# pc_to_pc_communication.net
KiCad netlist of a schematic drawn in EAGLE
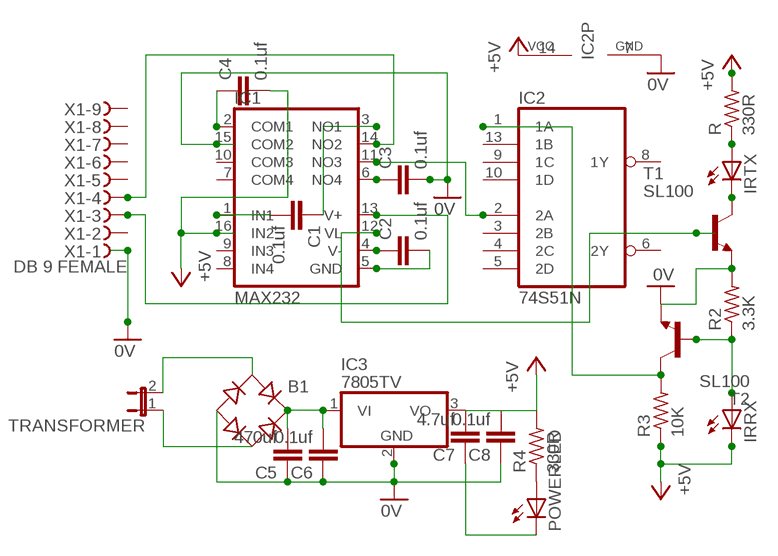
[diagram p0: schematic, sheet 1]

(export (version "E")
  (design (tool "Eeschema 10.0.6"))
  (components
    (comp (ref "B1")
      (value "B-DIL")
      (footprint "eagle-import:B-DIL")
      (libsource (lib "eagle-import") (part "B-DIL"))
    )
    (comp (ref "C1")
      (value "0.1uf")
      (footprint "eagle-import:C2.5-3")
      (libsource (lib "eagle-import") (part "C2,5-3"))
    )
    (comp (ref "C2")
      (value "0.1uf")
      (footprint "eagle-import:C2.5-3")
      (libsource (lib "eagle-import") (part "C2,5-3"))
    )
    (comp (ref "C3")
      (value "0.1uf")
      (footprint "eagle-import:C2.5-3")
      (libsource (lib "eagle-import") (part "C2,5-3"))
    )
    (comp (ref "C4")
      (value "0.1uf")
      (footprint "eagle-import:C2.5-3")
      (libsource (lib "eagle-import") (part "C2,5-3"))
    )
    (comp (ref "C5")
      (value "470uf")
      (footprint "eagle-import:C2.5-3")
      (libsource (lib "eagle-import") (part "C2,5-3"))
    )
    (comp (ref "C6")
      (value "0.1uf")
      (footprint "eagle-import:C2.5-3")
      (libsource (lib "eagle-import") (part "C2,5-3"))
    )
    (comp (ref "C7")
      (value "4.7uf")
      (footprint "eagle-import:C2.5-3")
      (libsource (lib "eagle-import") (part "C2,5-3"))
    )
    (comp (ref "C8")
      (value "0.1uf")
      (footprint "eagle-import:C2.5-3")
      (libsource (lib "eagle-import") (part "C2,5-3"))
    )
    (comp (ref "IC1")
      (value "MAX232")
      (footprint "eagle-import:DIL16")
      (fields (field (name "MPN") "MAX313EPE+"))
      (libsource (lib "eagle-import") (part "MAX313PEE"))
    )
    (comp (ref "IC2")
      (value "74S51N")
      (footprint "eagle-import:DIL14")
      (libsource (lib "eagle-import") (part "74S51N"))
    )
    (comp (ref "IC3")
      (value "7805TV")
      (footprint "eagle-import:TO220V")
      (libsource (lib "eagle-import") (part "78TV05"))
    )
    (comp (ref "IRRX")
      (value "LED3MM")
      (footprint "eagle-import:LED3MM")
      (libsource (lib "eagle-import") (part "LED3MM"))
    )
    (comp (ref "IRTX")
      (value "LED3MM")
      (footprint "eagle-import:LED3MM")
      (libsource (lib "eagle-import") (part "LED3MM"))
    )
    (comp (ref "POWERLED")
      (value "LED3MM")
      (footprint "eagle-import:LED3MM")
      (libsource (lib "eagle-import") (part "LED3MM"))
    )
    (comp (ref "R")
      (value "330R")
      (footprint "eagle-import:0204_7")
      (libsource (lib "eagle-import") (part "R-US_0204/7"))
    )
    (comp (ref "R2")
      (value "3.3K")
      (footprint "eagle-import:0204_7")
      (libsource (lib "eagle-import") (part "R-US_0204/7"))
    )
    (comp (ref "R3")
      (value "10K")
      (footprint "eagle-import:0204_7")
      (libsource (lib "eagle-import") (part "R-US_0204/7"))
    )
    (comp (ref "R4")
      (value "330R")
      (footprint "eagle-import:0204_7")
      (libsource (lib "eagle-import") (part "R-US_0204/7"))
    )
    (comp (ref "T1")
      (value "SL100")
      (footprint "eagle-import:TO5")
      (libsource (lib "eagle-import") (part "2N2102"))
    )
    (comp (ref "T2")
      (value "SL100")
      (footprint "eagle-import:TO5")
      (libsource (lib "eagle-import") (part "2N2102"))
    )
    (comp (ref "TRANSFORMER")
      (value "JP1E")
      (footprint "eagle-import:JP1")
      (libsource (lib "eagle-import") (part "JP1E"))
    )
    (comp (ref "X1")
      (value "DB 9 FEMALE")
      (footprint "eagle-import:H2M09ST")
      (libsource (lib "eagle-import") (part "D-SUB9-H2M09ST"))
    )
  )
  (nets
    (net (code "1") (name "+5V") (class "Default")
      (node (ref "C4") (pin "2") (pinfunction "2_2") (pintype "passive"))
      (node (ref "C7") (pin "2") (pinfunction "2_2") (pintype "passive"))
      (node (ref "C8") (pin "2") (pinfunction "2_2") (pintype "passive"))
      (node (ref "IC1") (pin "16") (pinfunction "IN2_16") (pintype "input"))
      (node (ref "IC2") (pin "14") (pinfunction "VCC_14") (pintype "power_in"))
      (node (ref "IC3") (pin "3") (pinfunction "VO_3") (pintype "passive"))
      (node (ref "IRRX") (pin "K") (pinfunction "C_K") (pintype "passive"))
      (node (ref "R") (pin "2") (pinfunction "2_2") (pintype "passive"))
      (node (ref "R3") (pin "1") (pinfunction "1_1") (pintype "passive"))
      (node (ref "R4") (pin "2") (pinfunction "2_2") (pintype "passive"))
    )
    (net (code "2") (name "0V") (class "Default")
      (node (ref "B1") (pin "-") (pinfunction "-_-") (pintype "passive"))
      (node (ref "C3") (pin "2") (pinfunction "2_2") (pintype "passive"))
      (node (ref "C5") (pin "1") (pinfunction "1_1") (pintype "passive"))
      (node (ref "C6") (pin "1") (pinfunction "1_1") (pintype "passive"))
      (node (ref "C7") (pin "1") (pinfunction "1_1") (pintype "passive"))
      (node (ref "C8") (pin "1") (pinfunction "1_1") (pintype "passive"))
      (node (ref "IC1") (pin "15") (pinfunction "COM2_15") (pintype "passive"))
      (node (ref "IC2") (pin "7") (pinfunction "GND_7") (pintype "power_in"))
      (node (ref "IC3") (pin "2") (pinfunction "GND_2") (pintype "passive"))
      (node (ref "POWERLED") (pin "K") (pinfunction "C_K") (pintype "passive"))
      (node (ref "R2") (pin "2") (pinfunction "2_2") (pintype "passive"))
      (node (ref "T1") (pin "1") (pinfunction "E_1") (pintype "passive"))
      (node (ref "T2") (pin "1") (pinfunction "E_1") (pintype "passive"))
      (node (ref "X1") (pin "1") (pinfunction "F_1") (pintype "passive"))
    )
    (net (code "3") (name "Net-(B1-PadAC1)") (class "Default")
      (node (ref "B1") (pin "AC1") (pinfunction "AC1_AC1") (pintype "passive"))
      (node (ref "TRANSFORMER") (pin "2") (pinfunction "2_2") (pintype "passive"))
    )
    (net (code "4") (name "Net-(B1-PadAC2)") (class "Default")
      (node (ref "B1") (pin "AC2") (pinfunction "AC2_AC2") (pintype "passive"))
      (node (ref "TRANSFORMER") (pin "1") (pinfunction "1_1") (pintype "passive"))
    )
    (net (code "5") (name "Net-(IC1-COM1)") (class "Default")
      (node (ref "C4") (pin "1") (pinfunction "1_1") (pintype "passive"))
      (node (ref "IC1") (pin "2") (pinfunction "COM1_2") (pintype "passive"))
    )
    (net (code "6") (name "Net-(IC1-GND)") (class "Default")
      (node (ref "C2") (pin "2") (pinfunction "2_2") (pintype "passive"))
      (node (ref "IC1") (pin "5") (pinfunction "GND_5") (pintype "power_in"))
    )
    (net (code "7") (name "Net-(IC1-IN1)") (class "Default")
      (node (ref "C1") (pin "2") (pinfunction "2_2") (pintype "passive"))
      (node (ref "IC1") (pin "1") (pinfunction "IN1_1") (pintype "input"))
    )
    (net (code "8") (name "Net-(IC1-NO1)") (class "Default")
      (node (ref "C1") (pin "1") (pinfunction "1_1") (pintype "passive"))
      (node (ref "IC1") (pin "3") (pinfunction "NO1_3") (pintype "passive"))
    )
    (net (code "9") (name "Net-(IC1-NO2)") (class "Default")
      (node (ref "IC1") (pin "14") (pinfunction "NO2_14") (pintype "passive"))
      (node (ref "X1") (pin "4") (pinfunction "F_4") (pintype "passive"))
    )
    (net (code "10") (name "Net-(IC1-NO3)") (class "Default")
      (node (ref "IC1") (pin "11") (pinfunction "NO3_11") (pintype "passive"))
      (node (ref "IC2") (pin "2") (pinfunction "2A_2") (pintype "input"))
    )
    (net (code "11") (name "Net-(IC1-NO4)") (class "Default")
      (node (ref "C3") (pin "1") (pinfunction "1_1") (pintype "passive"))
      (node (ref "IC1") (pin "6") (pinfunction "NO4_6") (pintype "passive"))
    )
    (net (code "12") (name "Net-(IC1-V+)") (class "Default")
      (node (ref "IC1") (pin "13") (pinfunction "V+_13") (pintype "power_in"))
      (node (ref "X1") (pin "3") (pinfunction "F_3") (pintype "passive"))
    )
    (net (code "13") (name "Net-(IC1-V-)") (class "Default")
      (node (ref "C2") (pin "1") (pinfunction "1_1") (pintype "passive"))
      (node (ref "IC1") (pin "4") (pinfunction "V-_4") (pintype "power_in"))
    )
    (net (code "14") (name "Net-(IC1-VL)") (class "Default")
      (node (ref "IC1") (pin "12") (pinfunction "VL_12") (pintype "power_in"))
      (node (ref "T1") (pin "2") (pinfunction "B_2") (pintype "passive"))
    )
    (net (code "15") (name "Net-(IC2A-1A)") (class "Default")
      (node (ref "IC2") (pin "1") (pinfunction "1A_1") (pintype "input"))
      (node (ref "R3") (pin "2") (pinfunction "2_2") (pintype "passive"))
      (node (ref "T2") (pin "3") (pinfunction "C_3") (pintype "passive"))
    )
    (net (code "16") (name "Net-(IC3-VI)") (class "Default")
      (node (ref "B1") (pin "+") (pinfunction "+_+") (pintype "passive"))
      (node (ref "C5") (pin "2") (pinfunction "2_2") (pintype "passive"))
      (node (ref "C6") (pin "2") (pinfunction "2_2") (pintype "passive"))
      (node (ref "IC3") (pin "1") (pinfunction "VI_1") (pintype "input"))
    )
    (net (code "17") (name "Net-(IRTX-C)") (class "Default")
      (node (ref "IRTX") (pin "K") (pinfunction "C_K") (pintype "passive"))
      (node (ref "T1") (pin "3") (pinfunction "C_3") (pintype "passive"))
    )
    (net (code "18") (name "Net-(IRTX-PadA)") (class "Default")
      (node (ref "IRTX") (pin "A") (pinfunction "A_A") (pintype "passive"))
      (node (ref "R") (pin "1") (pinfunction "1_1") (pintype "passive"))
    )
    (net (code "19") (name "Net-(POWERLED-PadA)") (class "Default")
      (node (ref "POWERLED") (pin "A") (pinfunction "A_A") (pintype "passive"))
      (node (ref "R4") (pin "1") (pinfunction "1_1") (pintype "passive"))
    )
    (net (code "20") (name "Net-(T2-B)") (class "Default")
      (node (ref "IRRX") (pin "A") (pinfunction "A_A") (pintype "passive"))
      (node (ref "R2") (pin "1") (pinfunction "1_1") (pintype "passive"))
      (node (ref "T2") (pin "2") (pinfunction "B_2") (pintype "passive"))
    )
    (net (code "21") (name "unconnected-(IC1-COM3-Pad10)") (class "Default")
      (node (ref "IC1") (pin "10") (pinfunction "COM3_10") (pintype "passive"))
    )
    (net (code "22") (name "unconnected-(IC1-COM4-Pad7)") (class "Default")
      (node (ref "IC1") (pin "7") (pinfunction "COM4_7") (pintype "passive"))
    )
    (net (code "23") (name "unconnected-(IC1-IN3-Pad9)") (class "Default")
      (node (ref "IC1") (pin "9") (pinfunction "IN3_9") (pintype "input"))
    )
    (net (code "24") (name "unconnected-(IC1-IN4-Pad8)") (class "Default")
      (node (ref "IC1") (pin "8") (pinfunction "IN4_8") (pintype "input"))
    )
    (net (code "25") (name "unconnected-(IC2A-1B-Pad13)") (class "Default")
      (node (ref "IC2") (pin "13") (pinfunction "1B_13") (pintype "input"))
    )
    (net (code "26") (name "unconnected-(IC2A-1C-Pad9)") (class "Default")
      (node (ref "IC2") (pin "9") (pinfunction "1C_9") (pintype "input"))
    )
    (net (code "27") (name "unconnected-(IC2A-1D-Pad10)") (class "Default")
      (node (ref "IC2") (pin "10") (pinfunction "1D_10") (pintype "input"))
    )
    (net (code "28") (name "unconnected-(IC2A-1Y-Pad8)") (class "Default")
      (node (ref "IC2") (pin "8") (pinfunction "1Y_8") (pintype "output"))
    )
    (net (code "29") (name "unconnected-(IC2A-2B-Pad3)") (class "Default")
      (node (ref "IC2") (pin "3") (pinfunction "2B_3") (pintype "input"))
    )
    (net (code "30") (name "unconnected-(IC2A-2C-Pad4)") (class "Default")
      (node (ref "IC2") (pin "4") (pinfunction "2C_4") (pintype "input"))
    )
    (net (code "31") (name "unconnected-(IC2A-2D-Pad5)") (class "Default")
      (node (ref "IC2") (pin "5") (pinfunction "2D_5") (pintype "input"))
    )
    (net (code "32") (name "unconnected-(IC2A-2Y-Pad6)") (class "Default")
      (node (ref "IC2") (pin "6") (pinfunction "2Y_6") (pintype "output"))
    )
    (net (code "33") (name "unconnected-(X1B-F-Pad2)") (class "Default")
      (node (ref "X1") (pin "2") (pinfunction "F_2") (pintype "passive"))
    )
    (net (code "34") (name "unconnected-(X1E-F-Pad5)") (class "Default")
      (node (ref "X1") (pin "5") (pinfunction "F_5") (pintype "passive"))
    )
    (net (code "35") (name "unconnected-(X1F-F-Pad6)") (class "Default")
      (node (ref "X1") (pin "6") (pinfunction "F_6") (pintype "passive"))
    )
    (net (code "36") (name "unconnected-(X1G-F-Pad7)") (class "Default")
      (node (ref "X1") (pin "7") (pinfunction "F_7") (pintype "passive"))
    )
    (net (code "37") (name "unconnected-(X1H-F-Pad8)") (class "Default")
      (node (ref "X1") (pin "8") (pinfunction "F_8") (pintype "passive"))
    )
    (net (code "38") (name "unconnected-(X1I-F-Pad9)") (class "Default")
      (node (ref "X1") (pin "9") (pinfunction "F_9") (pintype "passive"))
    )
  )
)
